# Scheda_motori_L298.net
KiCad netlist of a schematic drawn in EAGLE
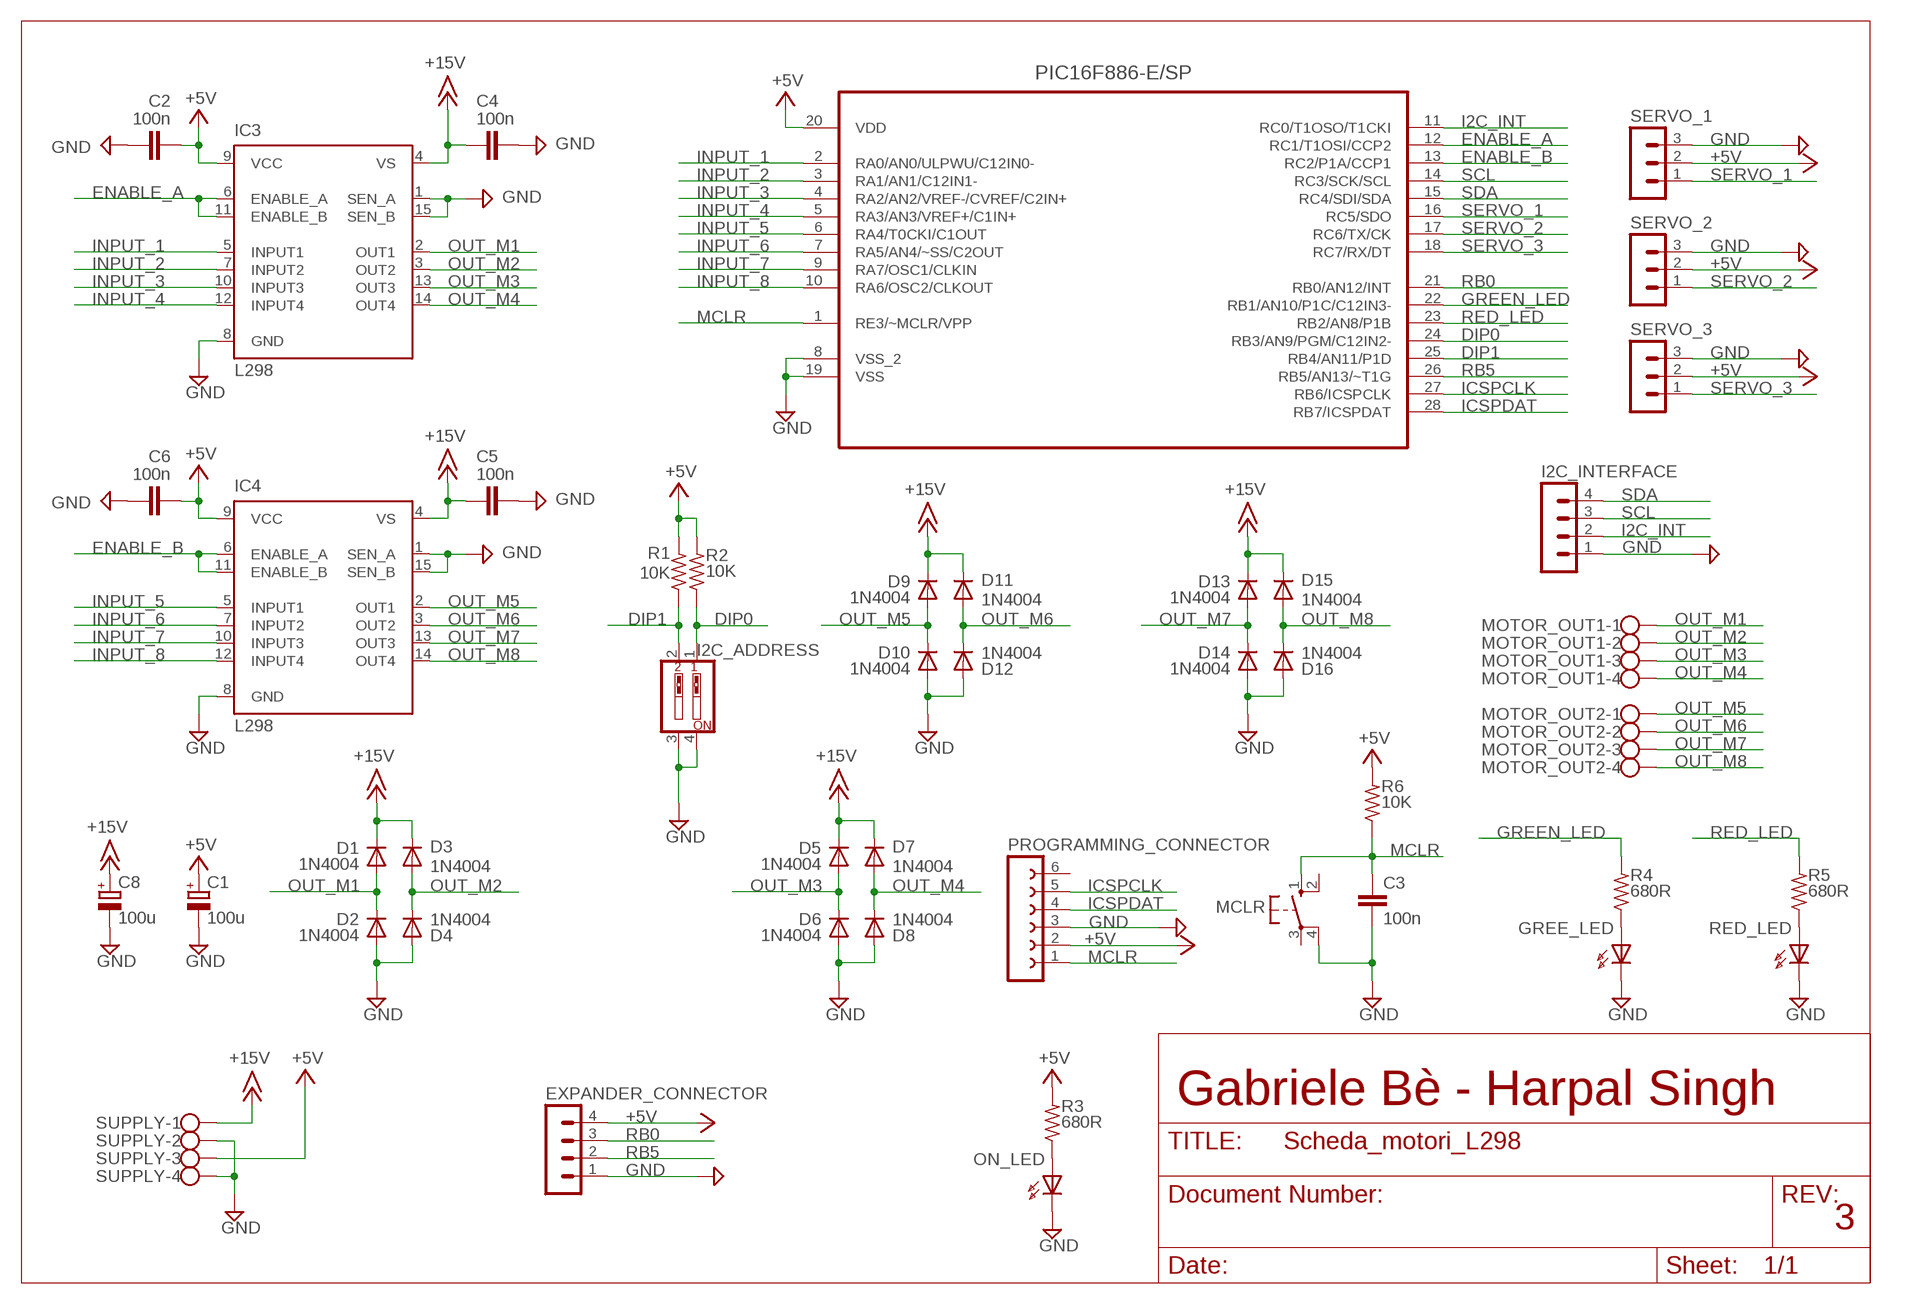
[diagram p0: schematic, sheet 1]

(export (version "E")
  (design (tool "Eeschema 10.0.6"))
  (components
    (comp (ref "C1")
      (value "100u")
      (footprint "eagle-import:E2,5-7")
      (libsource (lib "eagle-import") (part "CPOL-EUE2.5-7"))
    )
    (comp (ref "C2")
      (value "100n")
      (footprint "eagle-import:C050-024X044")
      (libsource (lib "eagle-import") (part "C-EU050-024X044"))
    )
    (comp (ref "C3")
      (value "100n")
      (footprint "eagle-import:C050-024X044")
      (libsource (lib "eagle-import") (part "C-EU050-024X044"))
    )
    (comp (ref "C4")
      (value "100n")
      (footprint "eagle-import:C050-024X044")
      (libsource (lib "eagle-import") (part "C-EU050-024X044"))
    )
    (comp (ref "C5")
      (value "100n")
      (footprint "eagle-import:C050-024X044")
      (libsource (lib "eagle-import") (part "C-EU050-024X044"))
    )
    (comp (ref "C6")
      (value "100n")
      (footprint "eagle-import:C050-024X044")
      (libsource (lib "eagle-import") (part "C-EU050-024X044"))
    )
    (comp (ref "C8")
      (value "100u")
      (footprint "eagle-import:E2,5-7")
      (libsource (lib "eagle-import") (part "CPOL-EUE2.5-7"))
    )
    (comp (ref "D1")
      (value "1N4004")
      (footprint "eagle-import:DO41-10")
      (libsource (lib "eagle-import") (part "1N4004"))
    )
    (comp (ref "D2")
      (value "1N4004")
      (footprint "eagle-import:DO41-10")
      (libsource (lib "eagle-import") (part "1N4004"))
    )
    (comp (ref "D3")
      (value "1N4004")
      (footprint "eagle-import:DO41-10")
      (libsource (lib "eagle-import") (part "1N4004"))
    )
    (comp (ref "D4")
      (value "1N4004")
      (footprint "eagle-import:DO41-10")
      (libsource (lib "eagle-import") (part "1N4004"))
    )
    (comp (ref "D5")
      (value "1N4004")
      (footprint "eagle-import:DO41-10")
      (libsource (lib "eagle-import") (part "1N4004"))
    )
    (comp (ref "D6")
      (value "1N4004")
      (footprint "eagle-import:DO41-10")
      (libsource (lib "eagle-import") (part "1N4004"))
    )
    (comp (ref "D7")
      (value "1N4004")
      (footprint "eagle-import:DO41-10")
      (libsource (lib "eagle-import") (part "1N4004"))
    )
    (comp (ref "D8")
      (value "1N4004")
      (footprint "eagle-import:DO41-10")
      (libsource (lib "eagle-import") (part "1N4004"))
    )
    (comp (ref "D9")
      (value "1N4004")
      (footprint "eagle-import:DO41-10")
      (libsource (lib "eagle-import") (part "1N4004"))
    )
    (comp (ref "D10")
      (value "1N4004")
      (footprint "eagle-import:DO41-10")
      (libsource (lib "eagle-import") (part "1N4004"))
    )
    (comp (ref "D11")
      (value "1N4004")
      (footprint "eagle-import:DO41-10")
      (libsource (lib "eagle-import") (part "1N4004"))
    )
    (comp (ref "D12")
      (value "1N4004")
      (footprint "eagle-import:DO41-10")
      (libsource (lib "eagle-import") (part "1N4004"))
    )
    (comp (ref "D13")
      (value "1N4004")
      (footprint "eagle-import:DO41-10")
      (libsource (lib "eagle-import") (part "1N4004"))
    )
    (comp (ref "D14")
      (value "1N4004")
      (footprint "eagle-import:DO41-10")
      (libsource (lib "eagle-import") (part "1N4004"))
    )
    (comp (ref "D15")
      (value "1N4004")
      (footprint "eagle-import:DO41-10")
      (libsource (lib "eagle-import") (part "1N4004"))
    )
    (comp (ref "D16")
      (value "1N4004")
      (footprint "eagle-import:DO41-10")
      (libsource (lib "eagle-import") (part "1N4004"))
    )
    (comp (ref "EXPANDER_CONNECTOR")
      (value "MA04-1")
      (footprint "eagle-import:MA04-1")
      (libsource (lib "eagle-import") (part "MA04-1"))
    )
    (comp (ref "GREE_LED")
      (value "HLMP6")
      (footprint "eagle-import:HLMP6")
      (fields (field (name "MF") "AGILENT TECHNOLOGIES") (field (name "MPN") "HLMP-6500"))
      (libsource (lib "eagle-import") (part "HLMP6"))
    )
    (comp (ref "I2C_ADDRESS")
      (value "SW_DIP-2")
      (footprint "eagle-import:EDG-02")
      (libsource (lib "eagle-import") (part "SW_DIP-2"))
    )
    (comp (ref "I2C_INTERFACE")
      (value "MA04-1")
      (footprint "eagle-import:MA04-1")
      (libsource (lib "eagle-import") (part "MA04-1"))
    )
    (comp (ref "IC3")
      (value "L298")
      (footprint "eagle-import:MULTIWATT-15")
      (libsource (lib "eagle-import") (part "L298"))
    )
    (comp (ref "IC4")
      (value "L298")
      (footprint "eagle-import:MULTIWATT-15")
      (libsource (lib "eagle-import") (part "L298"))
    )
    (comp (ref "MCLR")
      (value "10-XX")
      (footprint "eagle-import:B3F-10XX")
      (libsource (lib "eagle-import") (part "10-XX"))
    )
    (comp (ref "MOTOR_OUT1")
      (value "W237-4")
      (footprint "eagle-import:W237-4")
      (libsource (lib "eagle-import") (part "W237-4"))
    )
    (comp (ref "MOTOR_OUT2")
      (value "W237-4")
      (footprint "eagle-import:W237-4")
      (libsource (lib "eagle-import") (part "W237-4"))
    )
    (comp (ref "ON_LED")
      (value "HLMP6")
      (footprint "eagle-import:HLMP6")
      (fields (field (name "MF") "AGILENT TECHNOLOGIES") (field (name "MPN") "HLMP-6500"))
      (libsource (lib "eagle-import") (part "HLMP6"))
    )
    (comp (ref "PROGRAMMING_CONNECTOR")
      (value "FE06-1")
      (footprint "eagle-import:FE06")
      (libsource (lib "eagle-import") (part "FE06-1"))
    )
    (comp (ref "R1")
      (value "10K")
      (footprint "eagle-import:0207_10")
      (libsource (lib "eagle-import") (part "R-US_0207/10"))
    )
    (comp (ref "R2")
      (value "10K")
      (footprint "eagle-import:0207_10")
      (libsource (lib "eagle-import") (part "R-US_0207/10"))
    )
    (comp (ref "R3")
      (value "680R")
      (footprint "eagle-import:0207_10")
      (libsource (lib "eagle-import") (part "R-US_0207/10"))
    )
    (comp (ref "R4")
      (value "680R")
      (footprint "eagle-import:0207_10")
      (libsource (lib "eagle-import") (part "R-US_0207/10"))
    )
    (comp (ref "R5")
      (value "680R")
      (footprint "eagle-import:0207_10")
      (libsource (lib "eagle-import") (part "R-US_0207/10"))
    )
    (comp (ref "R6")
      (value "10K")
      (footprint "eagle-import:0207_10")
      (libsource (lib "eagle-import") (part "R-US_0207/10"))
    )
    (comp (ref "RED_LED")
      (value "HLMP6")
      (footprint "eagle-import:HLMP6")
      (fields (field (name "MF") "AGILENT TECHNOLOGIES") (field (name "MPN") "HLMP-6500"))
      (libsource (lib "eagle-import") (part "HLMP6"))
    )
    (comp (ref "SERVO_1")
      (value "MA03-1")
      (footprint "eagle-import:MA03-1")
      (libsource (lib "eagle-import") (part "MA03-1"))
    )
    (comp (ref "SERVO_2")
      (value "MA03-1")
      (footprint "eagle-import:MA03-1")
      (libsource (lib "eagle-import") (part "MA03-1"))
    )
    (comp (ref "SERVO_3")
      (value "MA03-1")
      (footprint "eagle-import:MA03-1")
      (libsource (lib "eagle-import") (part "MA03-1"))
    )
    (comp (ref "SUPPLY")
      (value "W237-4")
      (footprint "eagle-import:W237-4")
      (libsource (lib "eagle-import") (part "W237-4"))
    )
    (comp (ref "U$1")
      (value "PIC16F886-E/SP")
      (footprint "eagle-import:DIP254P762X508-28")
      (libsource (lib "eagle-import") (part "PIC16F886-E/SP"))
    )
  )
  (nets
    (net (code "1") (name "+5V") (class "Default")
      (node (ref "C1") (pin "+") (pinfunction "+_+") (pintype "passive"))
      (node (ref "C2") (pin "2") (pinfunction "2_2") (pintype "passive"))
      (node (ref "C6") (pin "2") (pinfunction "2_2") (pintype "passive"))
      (node (ref "EXPANDER_CONNECTOR") (pin "4") (pinfunction "4_4") (pintype "passive"))
      (node (ref "IC3") (pin "9") (pinfunction "VCC_9") (pintype "power_in"))
      (node (ref "IC4") (pin "9") (pinfunction "VCC_9") (pintype "power_in"))
      (node (ref "PROGRAMMING_CONNECTOR") (pin "2") (pinfunction "2_2") (pintype "passive"))
      (node (ref "R1") (pin "2") (pinfunction "2_2") (pintype "passive"))
      (node (ref "R2") (pin "2") (pinfunction "2_2") (pintype "passive"))
      (node (ref "R3") (pin "2") (pinfunction "2_2") (pintype "passive"))
      (node (ref "R6") (pin "2") (pinfunction "2_2") (pintype "passive"))
      (node (ref "SERVO_1") (pin "2") (pinfunction "2_2") (pintype "passive"))
      (node (ref "SERVO_2") (pin "2") (pinfunction "2_2") (pintype "passive"))
      (node (ref "SERVO_3") (pin "2") (pinfunction "2_2") (pintype "passive"))
      (node (ref "SUPPLY") (pin "3") (pinfunction "KL_3") (pintype "passive"))
      (node (ref "U$1") (pin "20") (pinfunction "VDD_20") (pintype "power_in"))
    )
    (net (code "2") (name "+15V") (class "Default")
      (node (ref "C4") (pin "1") (pinfunction "1_1") (pintype "passive"))
      (node (ref "C5") (pin "1") (pinfunction "1_1") (pintype "passive"))
      (node (ref "C8") (pin "+") (pinfunction "+_+") (pintype "passive"))
      (node (ref "D1") (pin "C") (pinfunction "C_C") (pintype "passive"))
      (node (ref "D11") (pin "C") (pinfunction "C_C") (pintype "passive"))
      (node (ref "D13") (pin "C") (pinfunction "C_C") (pintype "passive"))
      (node (ref "D15") (pin "C") (pinfunction "C_C") (pintype "passive"))
      (node (ref "D3") (pin "C") (pinfunction "C_C") (pintype "passive"))
      (node (ref "D5") (pin "C") (pinfunction "C_C") (pintype "passive"))
      (node (ref "D7") (pin "C") (pinfunction "C_C") (pintype "passive"))
      (node (ref "D9") (pin "C") (pinfunction "C_C") (pintype "passive"))
      (node (ref "IC3") (pin "4") (pinfunction "VS_4") (pintype "power_in"))
      (node (ref "IC4") (pin "4") (pinfunction "VS_4") (pintype "power_in"))
      (node (ref "SUPPLY") (pin "1") (pinfunction "KL_1") (pintype "passive"))
    )
    (net (code "3") (name "/DIP0") (class "Default")
      (node (ref "I2C_ADDRESS") (pin "1") (pinfunction "1_1") (pintype "passive"))
      (node (ref "R2") (pin "1") (pinfunction "1_1") (pintype "passive"))
      (node (ref "U$1") (pin "24") (pinfunction "RB3/AN9/PGM/C12IN2-_24") (pintype "bidirectional"))
    )
    (net (code "4") (name "/DIP1") (class "Default")
      (node (ref "I2C_ADDRESS") (pin "2") (pinfunction "2_2") (pintype "passive"))
      (node (ref "R1") (pin "1") (pinfunction "1_1") (pintype "passive"))
      (node (ref "U$1") (pin "25") (pinfunction "RB4/AN11/P1D_25") (pintype "bidirectional"))
    )
    (net (code "5") (name "/ENABLE_A") (class "Default")
      (node (ref "IC3") (pin "11") (pinfunction "ENABLE_B_11") (pintype "input"))
      (node (ref "IC3") (pin "6") (pinfunction "ENABLE_A_6") (pintype "input"))
      (node (ref "U$1") (pin "12") (pinfunction "RC1/T1OSI/CCP2_12") (pintype "bidirectional"))
    )
    (net (code "6") (name "/ENABLE_B") (class "Default")
      (node (ref "IC4") (pin "11") (pinfunction "ENABLE_B_11") (pintype "input"))
      (node (ref "IC4") (pin "6") (pinfunction "ENABLE_A_6") (pintype "input"))
      (node (ref "U$1") (pin "13") (pinfunction "RC2/P1A/CCP1_13") (pintype "bidirectional"))
    )
    (net (code "7") (name "/GREEN_LED") (class "Default")
      (node (ref "R4") (pin "2") (pinfunction "2_2") (pintype "passive"))
      (node (ref "U$1") (pin "22") (pinfunction "RB1/AN10/P1C/C12IN3-_22") (pintype "bidirectional"))
    )
    (net (code "8") (name "/I2C_INT") (class "Default")
      (node (ref "I2C_INTERFACE") (pin "2") (pinfunction "2_2") (pintype "passive"))
      (node (ref "U$1") (pin "11") (pinfunction "RC0/T1OSO/T1CKI_11") (pintype "bidirectional"))
    )
    (net (code "9") (name "/ICSPCLK") (class "Default")
      (node (ref "PROGRAMMING_CONNECTOR") (pin "5") (pinfunction "5_5") (pintype "passive"))
      (node (ref "U$1") (pin "27") (pinfunction "RB6/ICSPCLK_27") (pintype "bidirectional"))
    )
    (net (code "10") (name "/ICSPDAT") (class "Default")
      (node (ref "PROGRAMMING_CONNECTOR") (pin "4") (pinfunction "4_4") (pintype "passive"))
      (node (ref "U$1") (pin "28") (pinfunction "RB7/ICSPDAT_28") (pintype "bidirectional"))
    )
    (net (code "11") (name "/INPUT_1") (class "Default")
      (node (ref "IC3") (pin "5") (pinfunction "INPUT1_5") (pintype "input"))
      (node (ref "U$1") (pin "2") (pinfunction "RA0/AN0/ULPWU/C12IN0-_2") (pintype "bidirectional"))
    )
    (net (code "12") (name "/INPUT_2") (class "Default")
      (node (ref "IC3") (pin "7") (pinfunction "INPUT2_7") (pintype "input"))
      (node (ref "U$1") (pin "3") (pinfunction "RA1/AN1/C12IN1-_3") (pintype "bidirectional"))
    )
    (net (code "13") (name "/INPUT_3") (class "Default")
      (node (ref "IC3") (pin "10") (pinfunction "INPUT3_10") (pintype "input"))
      (node (ref "U$1") (pin "4") (pinfunction "RA2/AN2/VREF-/CVREF/C2IN+_4") (pintype "bidirectional"))
    )
    (net (code "14") (name "/INPUT_4") (class "Default")
      (node (ref "IC3") (pin "12") (pinfunction "INPUT4_12") (pintype "input"))
      (node (ref "U$1") (pin "5") (pinfunction "RA3/AN3/VREF+/C1IN+_5") (pintype "bidirectional"))
    )
    (net (code "15") (name "/INPUT_5") (class "Default")
      (node (ref "IC4") (pin "5") (pinfunction "INPUT1_5") (pintype "input"))
      (node (ref "U$1") (pin "6") (pinfunction "RA4/T0CKI/C1OUT_6") (pintype "bidirectional"))
    )
    (net (code "16") (name "/INPUT_6") (class "Default")
      (node (ref "IC4") (pin "7") (pinfunction "INPUT2_7") (pintype "input"))
      (node (ref "U$1") (pin "7") (pinfunction "RA5/AN4/~{SS/C2OUT}_7") (pintype "bidirectional"))
    )
    (net (code "17") (name "/INPUT_7") (class "Default")
      (node (ref "IC4") (pin "10") (pinfunction "INPUT3_10") (pintype "input"))
      (node (ref "U$1") (pin "9") (pinfunction "RA7/OSC1/CLKIN_9") (pintype "bidirectional"))
    )
    (net (code "18") (name "/INPUT_8") (class "Default")
      (node (ref "IC4") (pin "12") (pinfunction "INPUT4_12") (pintype "input"))
      (node (ref "U$1") (pin "10") (pinfunction "RA6/OSC2/CLKOUT_10") (pintype "bidirectional"))
    )
    (net (code "19") (name "/MCLR") (class "Default")
      (node (ref "C3") (pin "1") (pinfunction "1_1") (pintype "passive"))
      (node (ref "MCLR") (pin "1") (pinfunction "S_1") (pintype "passive"))
      (node (ref "PROGRAMMING_CONNECTOR") (pin "1") (pinfunction "1_1") (pintype "passive"))
      (node (ref "R6") (pin "1") (pinfunction "1_1") (pintype "passive"))
      (node (ref "U$1") (pin "1") (pinfunction "RE3/~{MCLR/VPP}_1") (pintype "input"))
    )
    (net (code "20") (name "/OUT_M1") (class "Default")
      (node (ref "D1") (pin "A") (pinfunction "A_A") (pintype "passive"))
      (node (ref "D2") (pin "C") (pinfunction "C_C") (pintype "passive"))
      (node (ref "IC3") (pin "2") (pinfunction "OUT1_2") (pintype "output"))
      (node (ref "MOTOR_OUT1") (pin "1") (pinfunction "KL_1") (pintype "passive"))
    )
    (net (code "21") (name "/OUT_M2") (class "Default")
      (node (ref "D3") (pin "A") (pinfunction "A_A") (pintype "passive"))
      (node (ref "D4") (pin "C") (pinfunction "C_C") (pintype "passive"))
      (node (ref "IC3") (pin "3") (pinfunction "OUT2_3") (pintype "output"))
      (node (ref "MOTOR_OUT1") (pin "2") (pinfunction "KL_2") (pintype "passive"))
    )
    (net (code "22") (name "/OUT_M3") (class "Default")
      (node (ref "D5") (pin "A") (pinfunction "A_A") (pintype "passive"))
      (node (ref "D6") (pin "C") (pinfunction "C_C") (pintype "passive"))
      (node (ref "IC3") (pin "13") (pinfunction "OUT3_13") (pintype "output"))
      (node (ref "MOTOR_OUT1") (pin "3") (pinfunction "KL_3") (pintype "passive"))
    )
    (net (code "23") (name "/OUT_M4") (class "Default")
      (node (ref "D7") (pin "A") (pinfunction "A_A") (pintype "passive"))
      (node (ref "D8") (pin "C") (pinfunction "C_C") (pintype "passive"))
      (node (ref "IC3") (pin "14") (pinfunction "OUT4_14") (pintype "output"))
      (node (ref "MOTOR_OUT1") (pin "4") (pinfunction "KL_4") (pintype "passive"))
    )
    (net (code "24") (name "/OUT_M5") (class "Default")
      (node (ref "D10") (pin "C") (pinfunction "C_C") (pintype "passive"))
      (node (ref "D9") (pin "A") (pinfunction "A_A") (pintype "passive"))
      (node (ref "IC4") (pin "2") (pinfunction "OUT1_2") (pintype "output"))
      (node (ref "MOTOR_OUT2") (pin "1") (pinfunction "KL_1") (pintype "passive"))
    )
    (net (code "25") (name "/OUT_M6") (class "Default")
      (node (ref "D11") (pin "A") (pinfunction "A_A") (pintype "passive"))
      (node (ref "D12") (pin "C") (pinfunction "C_C") (pintype "passive"))
      (node (ref "IC4") (pin "3") (pinfunction "OUT2_3") (pintype "output"))
      (node (ref "MOTOR_OUT2") (pin "2") (pinfunction "KL_2") (pintype "passive"))
    )
    (net (code "26") (name "/OUT_M7") (class "Default")
      (node (ref "D13") (pin "A") (pinfunction "A_A") (pintype "passive"))
      (node (ref "D14") (pin "C") (pinfunction "C_C") (pintype "passive"))
      (node (ref "IC4") (pin "13") (pinfunction "OUT3_13") (pintype "output"))
      (node (ref "MOTOR_OUT2") (pin "3") (pinfunction "KL_3") (pintype "passive"))
    )
    (net (code "27") (name "/OUT_M8") (class "Default")
      (node (ref "D15") (pin "A") (pinfunction "A_A") (pintype "passive"))
      (node (ref "D16") (pin "C") (pinfunction "C_C") (pintype "passive"))
      (node (ref "IC4") (pin "14") (pinfunction "OUT4_14") (pintype "output"))
      (node (ref "MOTOR_OUT2") (pin "4") (pinfunction "KL_4") (pintype "passive"))
    )
    (net (code "28") (name "/RB0") (class "Default")
      (node (ref "EXPANDER_CONNECTOR") (pin "3") (pinfunction "3_3") (pintype "passive"))
      (node (ref "U$1") (pin "21") (pinfunction "RB0/AN12/INT_21") (pintype "bidirectional"))
    )
    (net (code "29") (name "/RB5") (class "Default")
      (node (ref "EXPANDER_CONNECTOR") (pin "2") (pinfunction "2_2") (pintype "passive"))
      (node (ref "U$1") (pin "26") (pinfunction "RB5/AN13/~{T1G}_26") (pintype "bidirectional"))
    )
    (net (code "30") (name "/RED_LED") (class "Default")
      (node (ref "R5") (pin "2") (pinfunction "2_2") (pintype "passive"))
      (node (ref "U$1") (pin "23") (pinfunction "RB2/AN8/P1B_23") (pintype "bidirectional"))
    )
    (net (code "31") (name "/SCL") (class "Default")
      (node (ref "I2C_INTERFACE") (pin "3") (pinfunction "3_3") (pintype "passive"))
      (node (ref "U$1") (pin "14") (pinfunction "RC3/SCK/SCL_14") (pintype "bidirectional"))
    )
    (net (code "32") (name "/SDA") (class "Default")
      (node (ref "I2C_INTERFACE") (pin "4") (pinfunction "4_4") (pintype "passive"))
      (node (ref "U$1") (pin "15") (pinfunction "RC4/SDI/SDA_15") (pintype "bidirectional"))
    )
    (net (code "33") (name "/SERVO_1") (class "Default")
      (node (ref "SERVO_1") (pin "1") (pinfunction "1_1") (pintype "passive"))
      (node (ref "U$1") (pin "16") (pinfunction "RC5/SDO_16") (pintype "bidirectional"))
    )
    (net (code "34") (name "/SERVO_2") (class "Default")
      (node (ref "SERVO_2") (pin "1") (pinfunction "1_1") (pintype "passive"))
      (node (ref "U$1") (pin "17") (pinfunction "RC6/TX/CK_17") (pintype "bidirectional"))
    )
    (net (code "35") (name "/SERVO_3") (class "Default")
      (node (ref "SERVO_3") (pin "1") (pinfunction "1_1") (pintype "passive"))
      (node (ref "U$1") (pin "18") (pinfunction "RC7/RX/DT_18") (pintype "bidirectional"))
    )
    (net (code "36") (name "GND") (class "Default")
      (node (ref "C1") (pin "-") (pinfunction "-_-") (pintype "passive"))
      (node (ref "C2") (pin "1") (pinfunction "1_1") (pintype "passive"))
      (node (ref "C3") (pin "2") (pinfunction "2_2") (pintype "passive"))
      (node (ref "C4") (pin "2") (pinfunction "2_2") (pintype "passive"))
      (node (ref "C5") (pin "2") (pinfunction "2_2") (pintype "passive"))
      (node (ref "C6") (pin "1") (pinfunction "1_1") (pintype "passive"))
      (node (ref "C8") (pin "-") (pinfunction "-_-") (pintype "passive"))
      (node (ref "D10") (pin "A") (pinfunction "A_A") (pintype "passive"))
      (node (ref "D12") (pin "A") (pinfunction "A_A") (pintype "passive"))
      (node (ref "D14") (pin "A") (pinfunction "A_A") (pintype "passive"))
      (node (ref "D16") (pin "A") (pinfunction "A_A") (pintype "passive"))
      (node (ref "D2") (pin "A") (pinfunction "A_A") (pintype "passive"))
      (node (ref "D4") (pin "A") (pinfunction "A_A") (pintype "passive"))
      (node (ref "D6") (pin "A") (pinfunction "A_A") (pintype "passive"))
      (node (ref "D8") (pin "A") (pinfunction "A_A") (pintype "passive"))
      (node (ref "EXPANDER_CONNECTOR") (pin "1") (pinfunction "1_1") (pintype "passive"))
      (node (ref "GREE_LED") (pin "K") (pinfunction "K_K") (pintype "passive"))
      (node (ref "I2C_ADDRESS") (pin "3") (pinfunction "3_3") (pintype "passive"))
      (node (ref "I2C_ADDRESS") (pin "4") (pinfunction "4_4") (pintype "passive"))
      (node (ref "I2C_INTERFACE") (pin "1") (pinfunction "1_1") (pintype "passive"))
      (node (ref "IC3") (pin "1") (pinfunction "SEN_A_1") (pintype "input"))
      (node (ref "IC3") (pin "15") (pinfunction "SEN_B_15") (pintype "input"))
      (node (ref "IC3") (pin "8") (pinfunction "GND_8") (pintype "power_in"))
      (node (ref "IC4") (pin "1") (pinfunction "SEN_A_1") (pintype "input"))
      (node (ref "IC4") (pin "15") (pinfunction "SEN_B_15") (pintype "input"))
      (node (ref "IC4") (pin "8") (pinfunction "GND_8") (pintype "power_in"))
      (node (ref "MCLR") (pin "4") (pinfunction "P1_4") (pintype "passive"))
      (node (ref "ON_LED") (pin "K") (pinfunction "K_K") (pintype "passive"))
      (node (ref "PROGRAMMING_CONNECTOR") (pin "3") (pinfunction "3_3") (pintype "passive"))
      (node (ref "RED_LED") (pin "K") (pinfunction "K_K") (pintype "passive"))
      (node (ref "SERVO_1") (pin "3") (pinfunction "3_3") (pintype "passive"))
      (node (ref "SERVO_2") (pin "3") (pinfunction "3_3") (pintype "passive"))
      (node (ref "SERVO_3") (pin "3") (pinfunction "3_3") (pintype "passive"))
      (node (ref "SUPPLY") (pin "2") (pinfunction "KL_2") (pintype "passive"))
      (node (ref "SUPPLY") (pin "4") (pinfunction "KL_4") (pintype "passive"))
      (node (ref "U$1") (pin "19") (pinfunction "VSS_19") (pintype "passive"))
      (node (ref "U$1") (pin "8") (pinfunction "VSS_2_8") (pintype "passive"))
    )
    (net (code "37") (name "Net-(GREE_LED-PadA)") (class "Default")
      (node (ref "GREE_LED") (pin "A") (pinfunction "A_A") (pintype "passive"))
      (node (ref "R4") (pin "1") (pinfunction "1_1") (pintype "passive"))
    )
    (net (code "38") (name "Net-(ON_LED-PadA)") (class "Default")
      (node (ref "ON_LED") (pin "A") (pinfunction "A_A") (pintype "passive"))
      (node (ref "R3") (pin "1") (pinfunction "1_1") (pintype "passive"))
    )
    (net (code "39") (name "Net-(R5-Pad1)") (class "Default")
      (node (ref "R5") (pin "1") (pinfunction "1_1") (pintype "passive"))
      (node (ref "RED_LED") (pin "A") (pinfunction "A_A") (pintype "passive"))
    )
    (net (code "40") (name "unconnected-(MCLR-P-Pad3)") (class "Default")
      (node (ref "MCLR") (pin "3") (pinfunction "P_3") (pintype "passive"))
    )
    (net (code "41") (name "unconnected-(MCLR-S1-Pad2)") (class "Default")
      (node (ref "MCLR") (pin "2") (pinfunction "S1_2") (pintype "passive"))
    )
    (net (code "42") (name "unconnected-(PROGRAMMING_CONNECTOR-Pad6)") (class "Default")
      (node (ref "PROGRAMMING_CONNECTOR") (pin "6") (pinfunction "6_6") (pintype "passive"))
    )
  )
)
